# Iridium_9603_Beacon.net
KiCad netlist of a schematic drawn in EAGLE
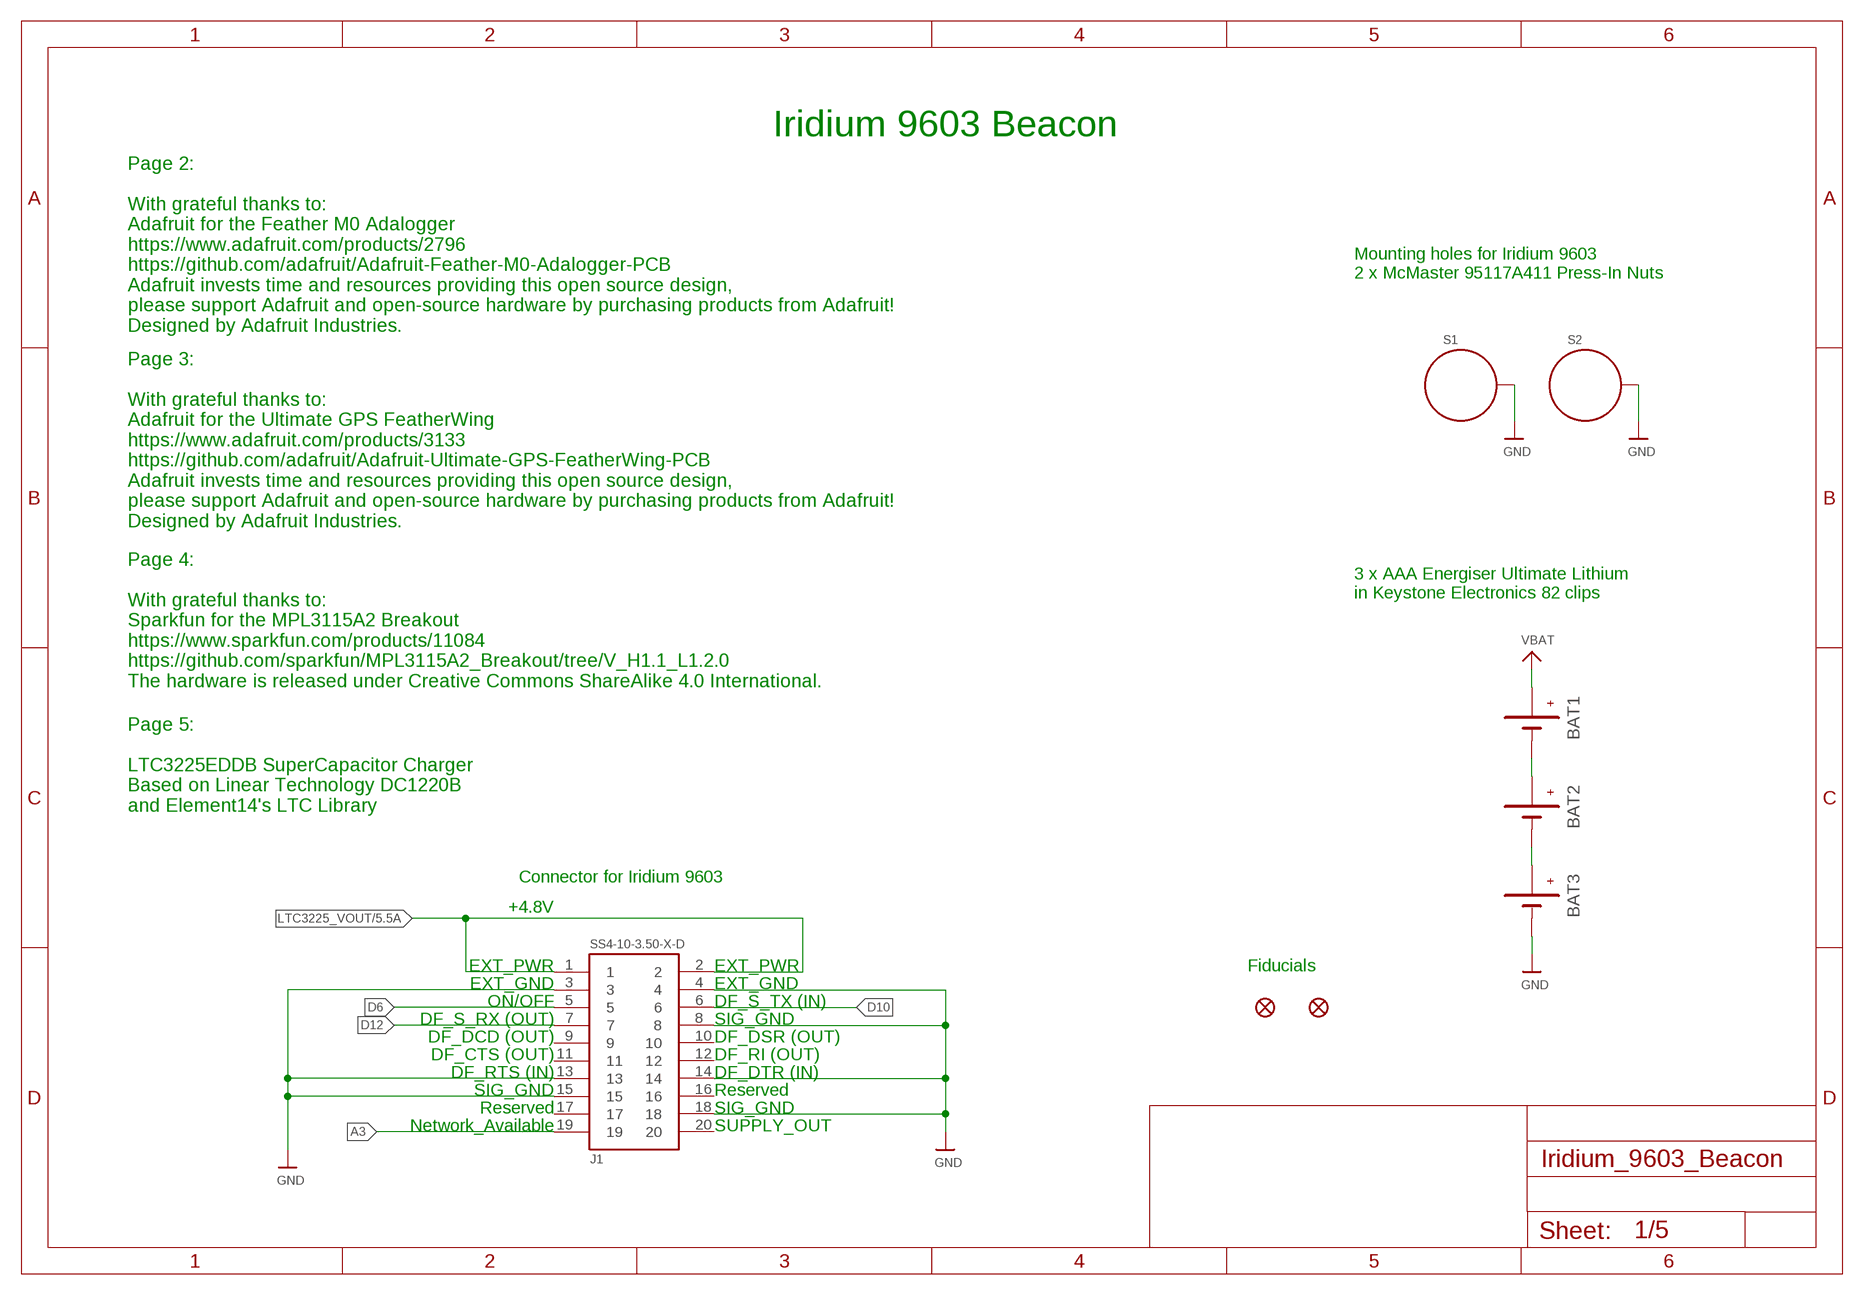
[diagram p0: schematic, sheet 1]
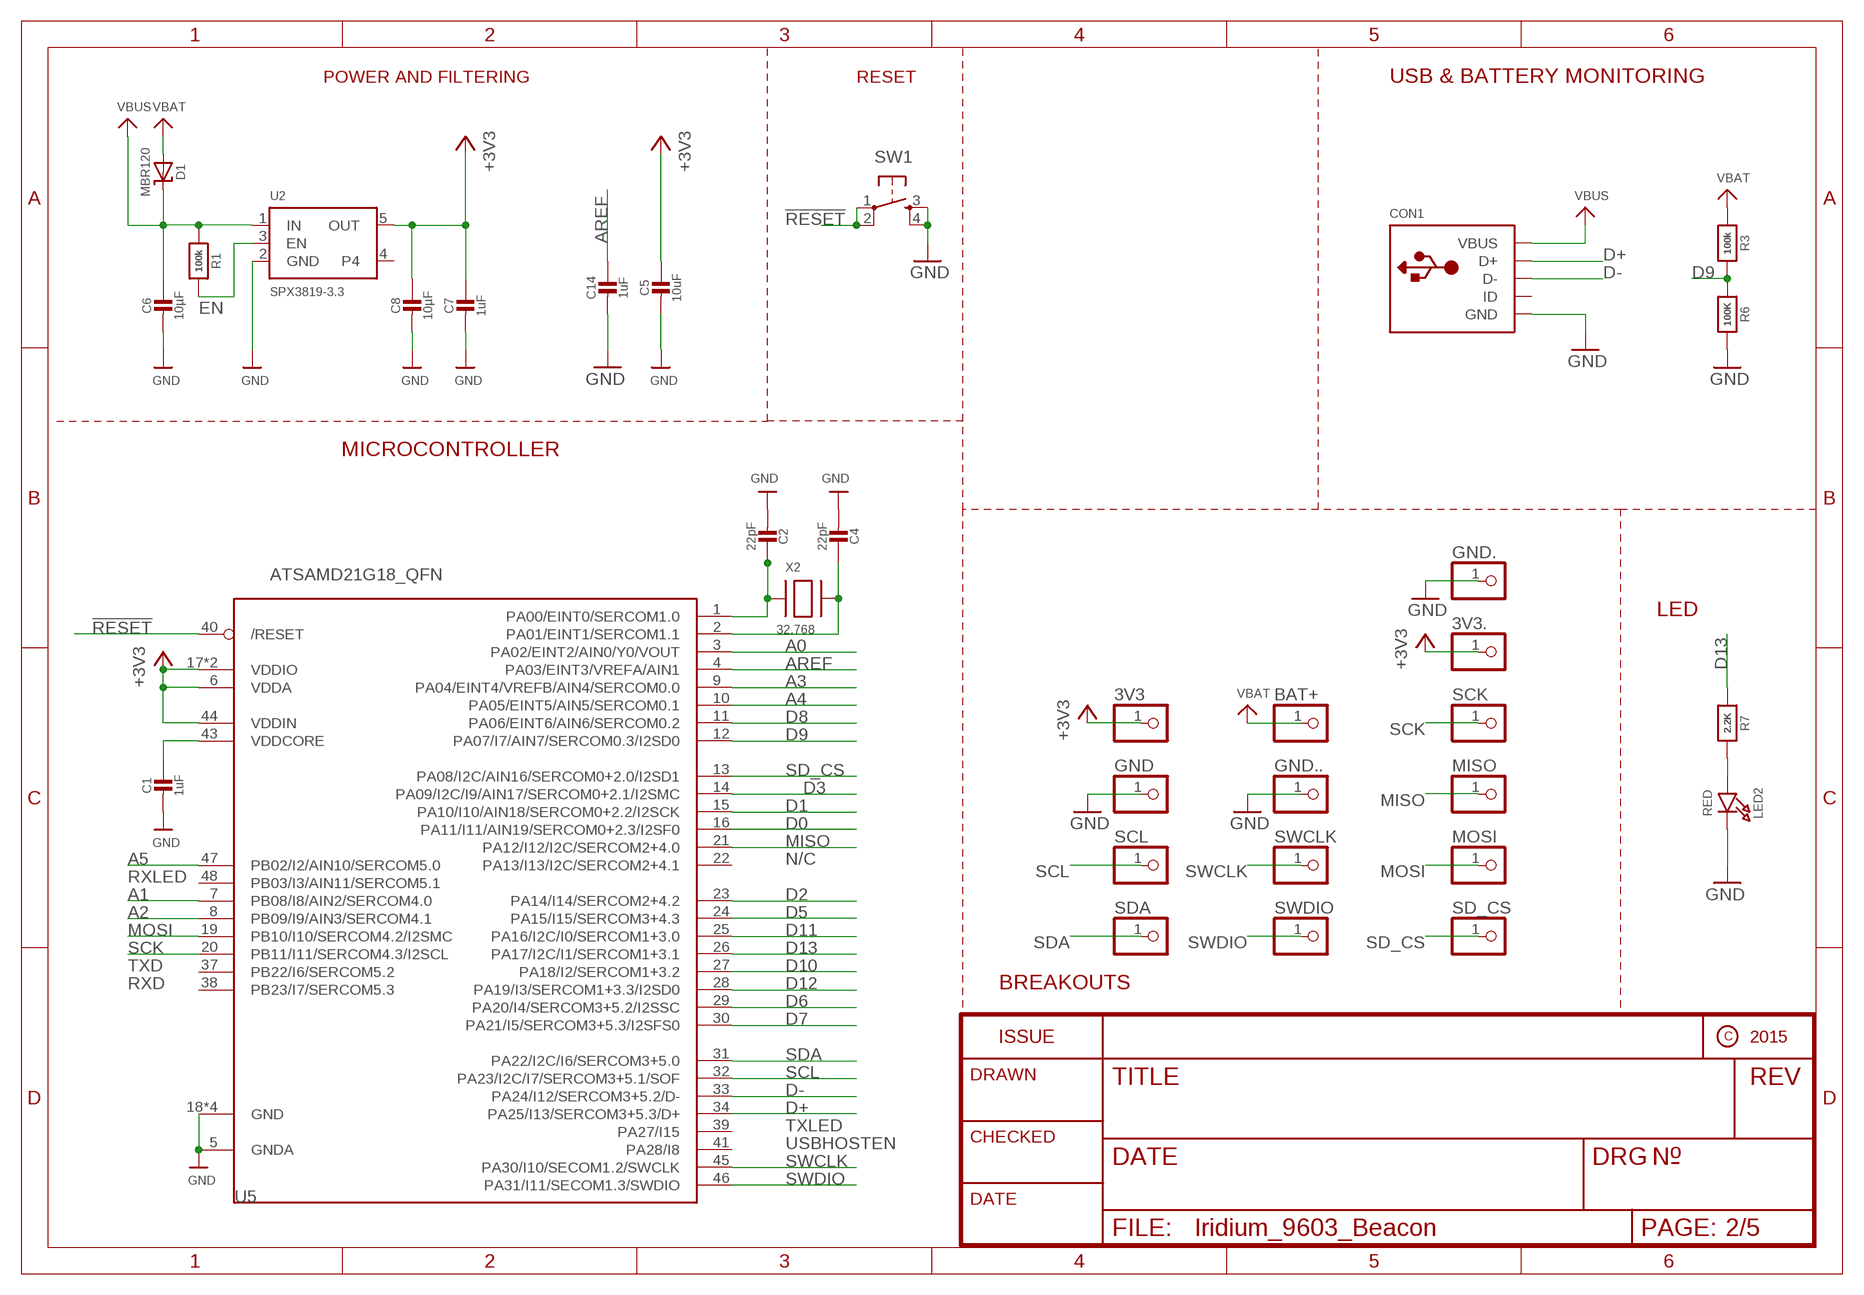
[diagram p1: schematic, sheet 2]
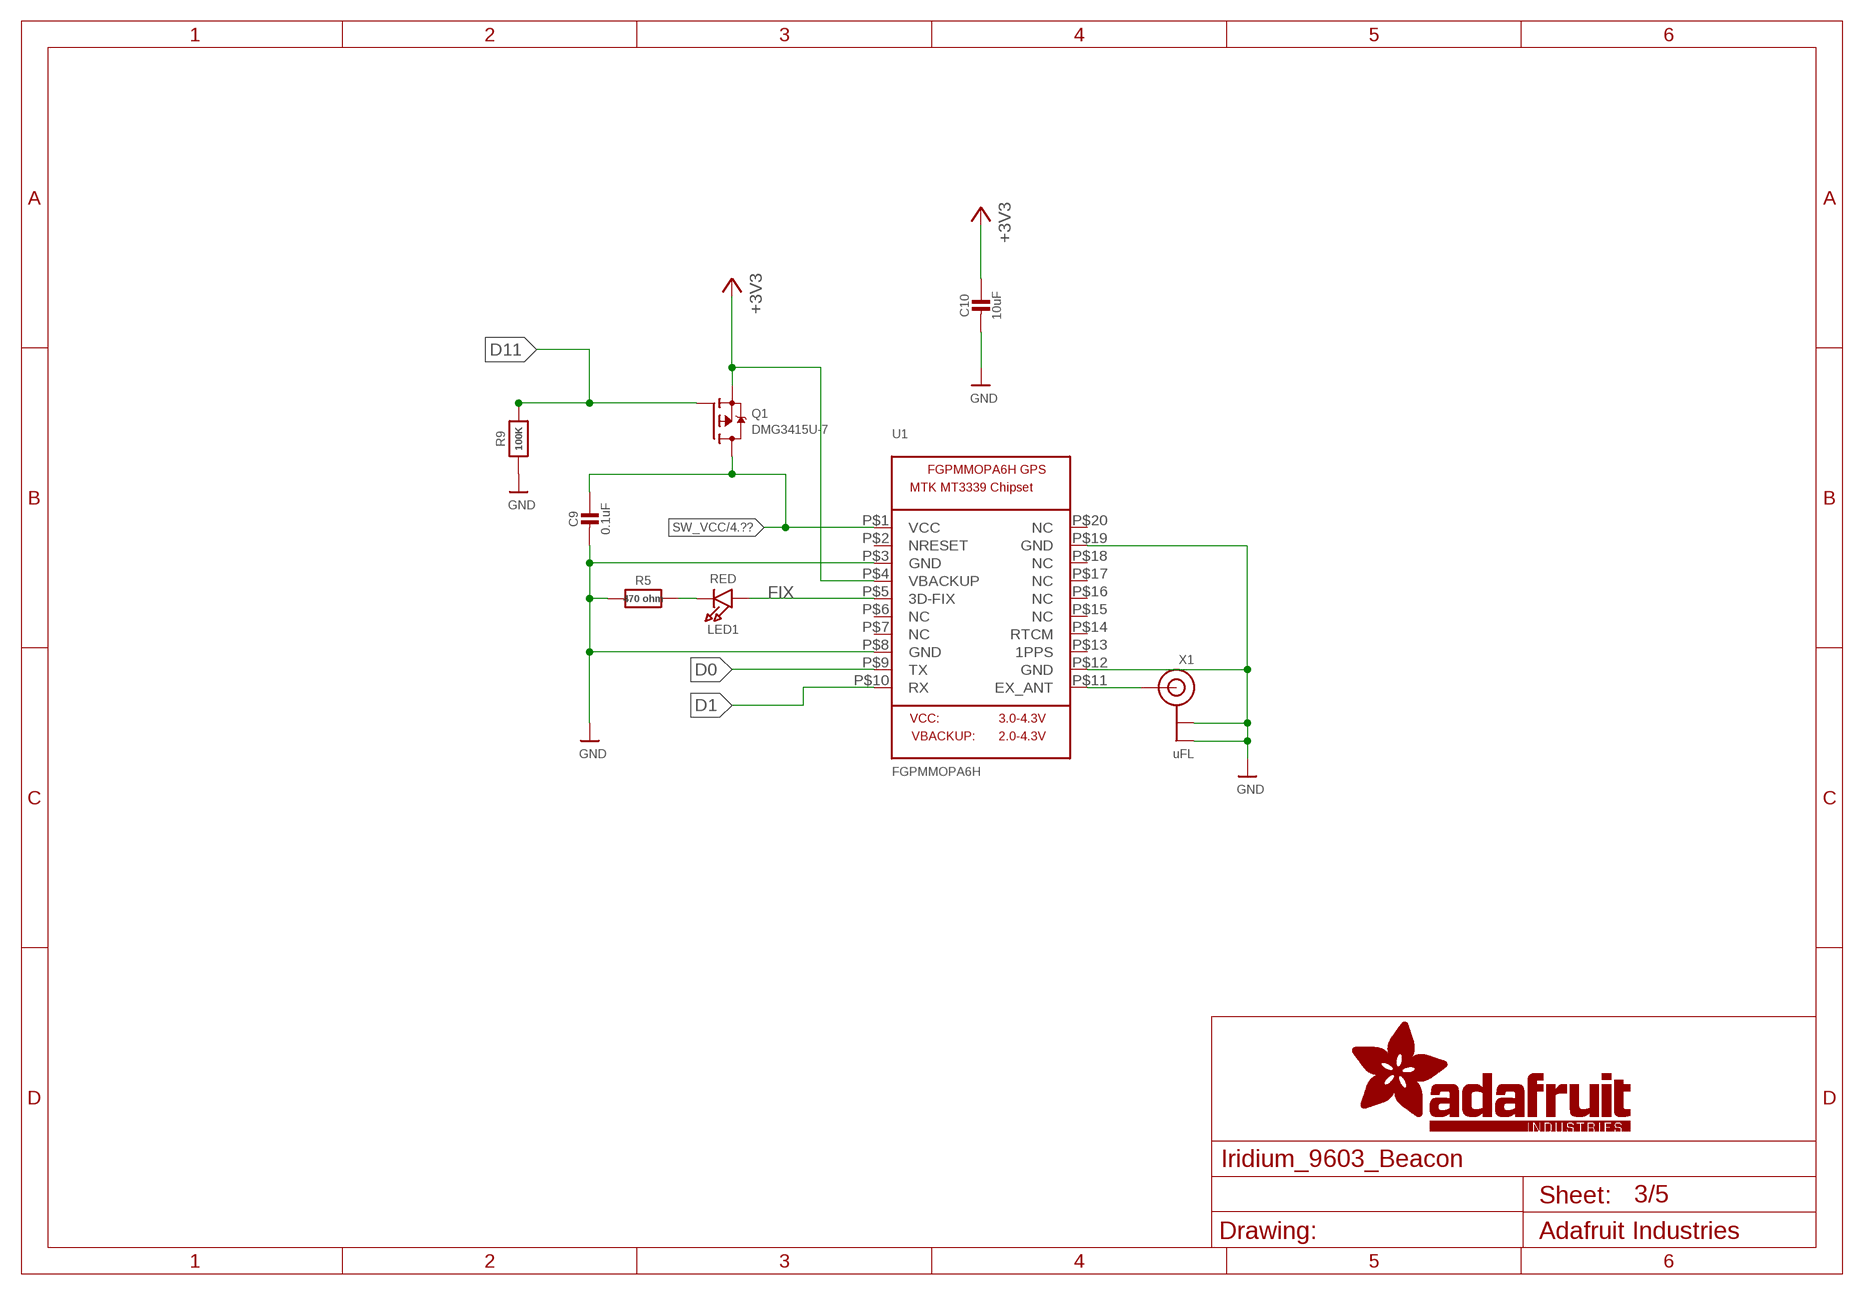
[diagram p2: schematic, sheet 3]
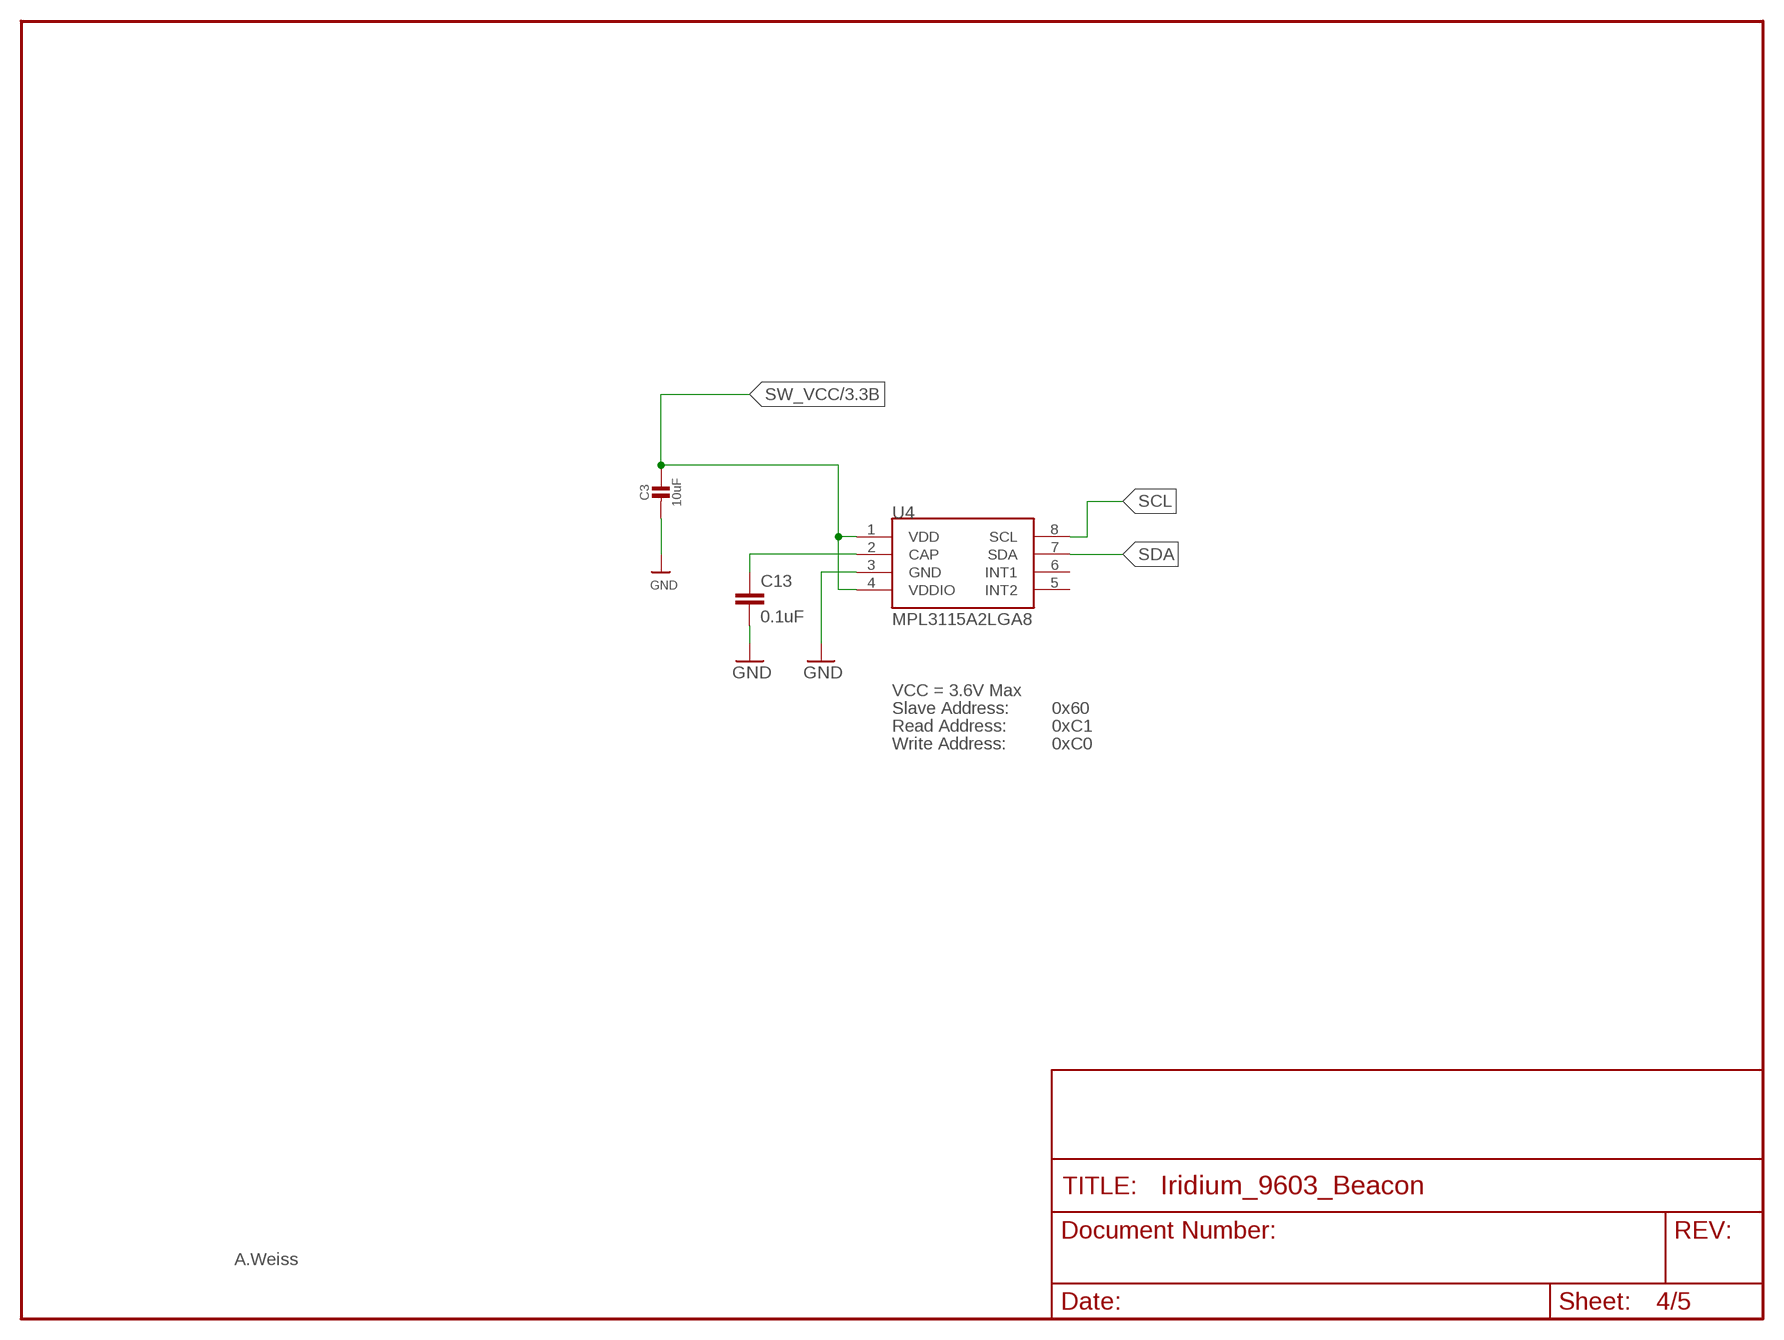
[diagram p3: schematic, sheet 4]
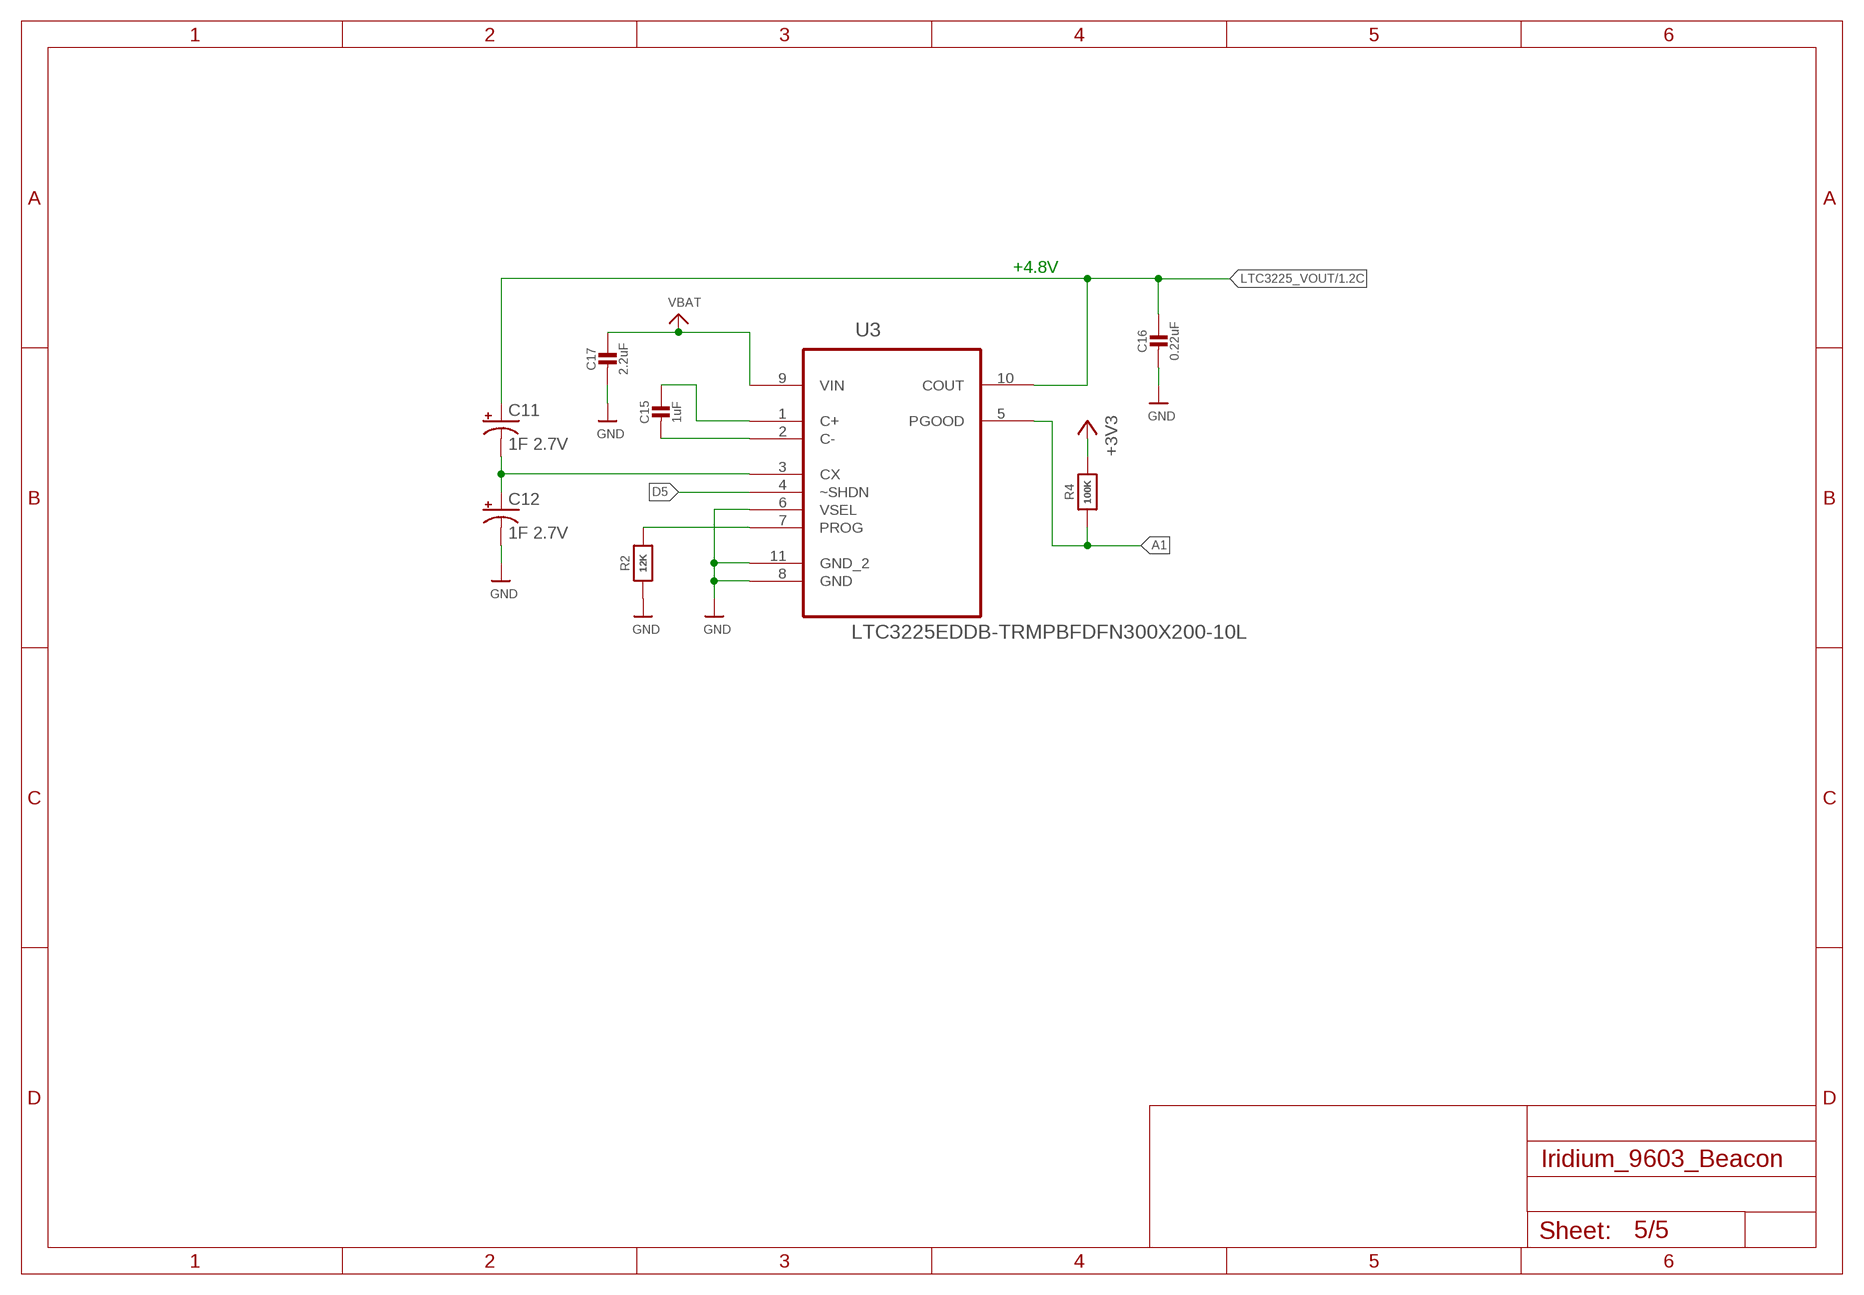
[diagram p4: schematic, sheet 5]

(export (version "E")
  (design (tool "Eeschema 10.0.6"))
  (components
    (comp (ref "C9")
      (value "0.1uF")
      (footprint "eagle-import:0805-NO")
      (libsource (lib "eagle-import") (part "CAP_CERAMIC0805-NOOUTLINE"))
    )
    (comp (ref "C10")
      (value "10uF")
      (footprint "eagle-import:0805-NO")
      (libsource (lib "eagle-import") (part "CAP_CERAMIC0805-NOOUTLINE"))
    )
    (comp (ref "LED1")
      (value "RED")
      (footprint "eagle-import:CHIPLED_0805_NOOUTLINE")
      (libsource (lib "eagle-import") (part "LED0805_NOOUTLINE"))
    )
    (comp (ref "Q1")
      (value "DMG3415U-7")
      (footprint "eagle-import:SOT23-WIDE")
      (libsource (lib "eagle-import") (part "MOSFET-PWIDE"))
    )
    (comp (ref "R5")
      (value "470 ohm")
      (footprint "eagle-import:0805-NO")
      (libsource (lib "eagle-import") (part "RESISTOR0805_NOOUTLINE"))
    )
    (comp (ref "R9")
      (value "100K")
      (footprint "eagle-import:0805-NO")
      (libsource (lib "eagle-import") (part "RESISTOR0805_NOOUTLINE"))
    )
    (comp (ref "U1")
      (value "FGPMMOPA6H")
      (footprint "eagle-import:FGPMMOPA6H")
      (libsource (lib "eagle-import") (part "GPS_FGPMMOPA6H"))
    )
    (comp (ref "X1")
      (value "uFL")
      (footprint "eagle-import:U.FL")
      (libsource (lib "eagle-import") (part "ANTENNA_U.FL"))
    )
    (comp (ref "C3")
      (value "10uF")
      (footprint "eagle-import:0805-NO")
      (libsource (lib "eagle-import") (part "CAP_CERAMIC0805-NOOUTLINE"))
    )
    (comp (ref "C13")
      (value "0.1uF")
      (footprint "eagle-import:0402-CAP")
      (libsource (lib "eagle-import") (part "CAP0402-CAP"))
    )
    (comp (ref "U4")
      (value "MPL3115A2LGA8")
      (footprint "eagle-import:LGA8")
      (libsource (lib "eagle-import") (part "MPL3115A2LGA8"))
    )
    (comp (ref "BAT1")
      (value "BATTERYKEYSTONE82")
      (footprint "eagle-import:BATTERY-AAA-KEYSTONE82")
      (libsource (lib "eagle-import") (part "BATTERYKEYSTONE82"))
    )
    (comp (ref "BAT2")
      (value "BATTERYKEYSTONE82")
      (footprint "eagle-import:BATTERY-AAA-KEYSTONE82")
      (libsource (lib "eagle-import") (part "BATTERYKEYSTONE82"))
    )
    (comp (ref "BAT3")
      (value "BATTERYKEYSTONE82")
      (footprint "eagle-import:BATTERY-AAA-KEYSTONE82")
      (libsource (lib "eagle-import") (part "BATTERYKEYSTONE82"))
    )
    (comp (ref "FD1")
      (value "FIDUCIAL1X2")
      (footprint "eagle-import:FIDUCIAL-1X2")
      (libsource (lib "eagle-import") (part "FIDUCIAL1X2"))
    )
    (comp (ref "FD2")
      (value "FIDUCIAL1X2")
      (footprint "eagle-import:FIDUCIAL-1X2")
      (libsource (lib "eagle-import") (part "FIDUCIAL1X2"))
    )
    (comp (ref "J1")
      (value "SS4-10-3.50-X-D")
      (footprint "eagle-import:SS4-10-3.50-X-D")
      (libsource (lib "eagle-import") (part "SS4-10-3.50-X-D"))
    )
    (comp (ref "S1")
      (value "STANDOFF_ELECTRICALMCMASTER-95117A411")
      (footprint "eagle-import:STANDOFF-ELECTRICAL-MCMASTER-95117A411")
      (libsource (lib "eagle-import") (part "STANDOFF_ELECTRICALMCMASTER-95117A411"))
    )
    (comp (ref "S2")
      (value "STANDOFF_ELECTRICALMCMASTER-95117A411")
      (footprint "eagle-import:STANDOFF-ELECTRICAL-MCMASTER-95117A411")
      (libsource (lib "eagle-import") (part "STANDOFF_ELECTRICALMCMASTER-95117A411"))
    )
    (comp (ref "C11")
      (value "1F 2.7V")
      (footprint "eagle-import:CPOL-RADIAL-1F-2.7V")
      (libsource (lib "eagle-import") (part "1F-2.7V(PTH)CPOL-RADIAL-1H-2.7V"))
    )
    (comp (ref "C12")
      (value "1F 2.7V")
      (footprint "eagle-import:CPOL-RADIAL-1F-2.7V")
      (libsource (lib "eagle-import") (part "1F-2.7V(PTH)CPOL-RADIAL-1H-2.7V"))
    )
    (comp (ref "C15")
      (value "1uF")
      (footprint "eagle-import:0603-NO")
      (libsource (lib "eagle-import") (part "CAP_CERAMIC0603_NO"))
    )
    (comp (ref "C16")
      (value "0.22uF")
      (footprint "eagle-import:0603-NO")
      (libsource (lib "eagle-import") (part "CAP_CERAMIC0603_NO"))
    )
    (comp (ref "C17")
      (value "2.2uF")
      (footprint "eagle-import:0805-NO")
      (libsource (lib "eagle-import") (part "CAP_CERAMIC0805-NOOUTLINE"))
    )
    (comp (ref "R2")
      (value "12K")
      (footprint "eagle-import:0805-NO")
      (libsource (lib "eagle-import") (part "RESISTOR0805_NOOUTLINE"))
    )
    (comp (ref "R4")
      (value "100K")
      (footprint "eagle-import:0805-NO")
      (libsource (lib "eagle-import") (part "RESISTOR0805_NOOUTLINE"))
    )
    (comp (ref "U3")
      (value "LTC3225EDDB-TRMPBFDFN300X200-10L")
      (footprint "eagle-import:DFN300X200-10L")
      (libsource (lib "eagle-import") (part "LTC3225EDDB-TRMPBFDFN300X200-10L"))
    )
    (comp (ref "3V3")
      (value "PINHD-1X1")
      (footprint "eagle-import:1X01")
      (libsource (lib "eagle-import") (part "PINHD-1X1"))
    )
    (comp (ref "3V3.")
      (value "PINHD-1X1")
      (footprint "eagle-import:1X01")
      (libsource (lib "eagle-import") (part "PINHD-1X1"))
    )
    (comp (ref "BAT+")
      (value "PINHD-1X1")
      (footprint "eagle-import:1X01")
      (libsource (lib "eagle-import") (part "PINHD-1X1"))
    )
    (comp (ref "C1")
      (value "1uF")
      (footprint "eagle-import:0603-NO")
      (libsource (lib "eagle-import") (part "CAP_CERAMIC0603_NO"))
    )
    (comp (ref "C2")
      (value "22pF")
      (footprint "eagle-import:0603-NO")
      (libsource (lib "eagle-import") (part "CAP_CERAMIC0603_NO"))
    )
    (comp (ref "C4")
      (value "22pF")
      (footprint "eagle-import:0603-NO")
      (libsource (lib "eagle-import") (part "CAP_CERAMIC0603_NO"))
    )
    (comp (ref "C5")
      (value "10uF")
      (footprint "eagle-import:0805-NO")
      (libsource (lib "eagle-import") (part "CAP_CERAMIC0805-NOOUTLINE"))
    )
    (comp (ref "C6")
      (value "10µF")
      (footprint "eagle-import:0805-NO")
      (libsource (lib "eagle-import") (part "CAP_CERAMIC0805-NOOUTLINE"))
    )
    (comp (ref "C7")
      (value "1uF")
      (footprint "eagle-import:0603-NO")
      (libsource (lib "eagle-import") (part "CAP_CERAMIC0603_NO"))
    )
    (comp (ref "C8")
      (value "10µF")
      (footprint "eagle-import:0805-NO")
      (libsource (lib "eagle-import") (part "CAP_CERAMIC0805-NOOUTLINE"))
    )
    (comp (ref "C14")
      (value "1uF")
      (footprint "eagle-import:0603-NO")
      (libsource (lib "eagle-import") (part "CAP_CERAMIC0603_NO"))
    )
    (comp (ref "CON1")
      (value "USBFCI_10103594")
      (footprint "eagle-import:FCI_10103594")
      (libsource (lib "eagle-import") (part "USBFCI_10103594"))
    )
    (comp (ref "D1")
      (value "MBR120")
      (footprint "eagle-import:SOD-123")
      (libsource (lib "eagle-import") (part "DIODE-SCHOTTKYSOD-123"))
    )
    (comp (ref "GND")
      (value "PINHD-1X1")
      (footprint "eagle-import:1X01")
      (libsource (lib "eagle-import") (part "PINHD-1X1"))
    )
    (comp (ref "GND.")
      (value "PINHD-1X1")
      (footprint "eagle-import:1X01")
      (libsource (lib "eagle-import") (part "PINHD-1X1"))
    )
    (comp (ref "GND..")
      (value "PINHD-1X1")
      (footprint "eagle-import:1X01")
      (libsource (lib "eagle-import") (part "PINHD-1X1"))
    )
    (comp (ref "LED2")
      (value "RED")
      (footprint "eagle-import:CHIPLED_0805_NOOUTLINE")
      (libsource (lib "eagle-import") (part "LED0805_NOOUTLINE"))
    )
    (comp (ref "MISO")
      (value "PINHD-1X1")
      (footprint "eagle-import:1X01")
      (libsource (lib "eagle-import") (part "PINHD-1X1"))
    )
    (comp (ref "MOSI")
      (value "PINHD-1X1")
      (footprint "eagle-import:1X01")
      (libsource (lib "eagle-import") (part "PINHD-1X1"))
    )
    (comp (ref "R1")
      (value "100k")
      (footprint "eagle-import:0603-NO")
      (libsource (lib "eagle-import") (part "RESISTOR_0603_NOOUT"))
    )
    (comp (ref "R3")
      (value "100k")
      (footprint "eagle-import:0603-NO")
      (libsource (lib "eagle-import") (part "RESISTOR_0603_NOOUT"))
    )
    (comp (ref "R6")
      (value "100K")
      (footprint "eagle-import:0603-NO")
      (libsource (lib "eagle-import") (part "RESISTOR_0603_NOOUT"))
    )
    (comp (ref "R7")
      (value "2.2K")
      (footprint "eagle-import:0603-NO")
      (libsource (lib "eagle-import") (part "RESISTOR_0603_NOOUT"))
    )
    (comp (ref "SCK")
      (value "PINHD-1X1")
      (footprint "eagle-import:1X01")
      (libsource (lib "eagle-import") (part "PINHD-1X1"))
    )
    (comp (ref "SCL")
      (value "PINHD-1X1")
      (footprint "eagle-import:1X01")
      (libsource (lib "eagle-import") (part "PINHD-1X1"))
    )
    (comp (ref "SDA")
      (value "PINHD-1X1")
      (footprint "eagle-import:1X01")
      (libsource (lib "eagle-import") (part "PINHD-1X1"))
    )
    (comp (ref "SD_CS")
      (value "PINHD-1X1")
      (footprint "eagle-import:1X01")
      (libsource (lib "eagle-import") (part "PINHD-1X1"))
    )
    (comp (ref "SW1")
      (value "SWITCH_SPST_4_PINRECT")
      (footprint "eagle-import:TACTILE_SWITCH_SMD_4.6X2.8MM")
      (libsource (lib "eagle-import") (part "SWITCH_SPST_4_PINRECT"))
    )
    (comp (ref "SWCLK")
      (value "PINHD-1X1")
      (footprint "eagle-import:1X01")
      (libsource (lib "eagle-import") (part "PINHD-1X1"))
    )
    (comp (ref "SWDIO")
      (value "PINHD-1X1")
      (footprint "eagle-import:1X01")
      (libsource (lib "eagle-import") (part "PINHD-1X1"))
    )
    (comp (ref "U2")
      (value "SPX3819-3.3")
      (footprint "eagle-import:SOT23-5")
      (libsource (lib "eagle-import") (part "VREG_SOT23-5"))
    )
    (comp (ref "U5")
      (value "ATSAMD21G18_QFN")
      (footprint "eagle-import:TQFN48_7MM")
      (libsource (lib "eagle-import") (part "ATSAMD21J_QFN"))
    )
    (comp (ref "X2")
      (value "32.768")
      (footprint "eagle-import:XTAL3215")
      (libsource (lib "eagle-import") (part "XTAL-3.2X1.5"))
    )
  )
  (nets
    (net (code "1") (name "+3V3") (class "Default")
      (node (ref "3V3") (pin "1") (pinfunction "1_1") (pintype "passive"))
      (node (ref "3V3.") (pin "1") (pinfunction "1_1") (pintype "passive"))
      (node (ref "C10") (pin "1") (pinfunction "1_1") (pintype "passive"))
      (node (ref "C5") (pin "1") (pinfunction "1_1") (pintype "passive"))
      (node (ref "C7") (pin "1") (pinfunction "1_1") (pintype "passive"))
      (node (ref "C8") (pin "1") (pinfunction "1_1") (pintype "passive"))
      (node (ref "Q1") (pin "2") (pinfunction "S_2") (pintype "passive"))
      (node (ref "R4") (pin "2") (pinfunction "2_2") (pintype "passive"))
      (node (ref "U1") (pin "P$4") (pinfunction "VBACKUP_P$4") (pintype "bidirectional"))
      (node (ref "U2") (pin "5") (pinfunction "OUT_5") (pintype "power_in"))
      (node (ref "U5") (pin "17") (pinfunction "VDDIO_17") (pintype "power_in"))
      (node (ref "U5") (pin "36") (pinfunction "VDDIO_36") (pintype "power_in"))
      (node (ref "U5") (pin "44") (pinfunction "VDDIN_44") (pintype "power_in"))
      (node (ref "U5") (pin "6") (pinfunction "VDDA_6") (pintype "power_in"))
    )
    (net (code "2") (name "A0") (class "Default")
      (node (ref "U5") (pin "3") (pinfunction "PA02/EINT2/AIN0/Y0/VOUT_3") (pintype "bidirectional"))
    )
    (net (code "3") (name "A1") (class "Default")
      (node (ref "R4") (pin "1") (pinfunction "1_1") (pintype "passive"))
      (node (ref "U3") (pin "5") (pinfunction "PGOOD_5") (pintype "output"))
      (node (ref "U5") (pin "7") (pinfunction "PB08/I8/AIN2/SERCOM4.0_7") (pintype "bidirectional"))
    )
    (net (code "4") (name "A2") (class "Default")
      (node (ref "U5") (pin "8") (pinfunction "PB09/I9/AIN3/SERCOM4.1_8") (pintype "bidirectional"))
    )
    (net (code "5") (name "A3") (class "Default")
      (node (ref "J1") (pin "19") (pinfunction "19_19") (pintype "bidirectional"))
      (node (ref "U5") (pin "9") (pinfunction "PA04/EINT4/VREFB/AIN4/SERCOM0.0_9") (pintype "bidirectional"))
    )
    (net (code "6") (name "A4") (class "Default")
      (node (ref "U5") (pin "10") (pinfunction "PA05/EINT5/AIN5/SERCOM0.1_10") (pintype "bidirectional"))
    )
    (net (code "7") (name "A5") (class "Default")
      (node (ref "U5") (pin "47") (pinfunction "PB02/I2/AIN10/SERCOM5.0_47") (pintype "bidirectional"))
    )
    (net (code "8") (name "AREF") (class "Default")
      (node (ref "C14") (pin "1") (pinfunction "1_1") (pintype "passive"))
      (node (ref "U5") (pin "4") (pinfunction "PA03/EINT3/VREFA/AIN1_4") (pintype "bidirectional"))
    )
    (net (code "9") (name "D+") (class "Default")
      (node (ref "CON1") (pin "D+") (pinfunction "D+_D+") (pintype "bidirectional"))
      (node (ref "U5") (pin "34") (pinfunction "PA25/I13/SERCOM3+5.3/D+_34") (pintype "bidirectional"))
    )
    (net (code "10") (name "D-") (class "Default")
      (node (ref "CON1") (pin "D-") (pinfunction "D-_D-") (pintype "bidirectional"))
      (node (ref "U5") (pin "33") (pinfunction "PA24/I12/SERCOM3+5.2/D-_33") (pintype "bidirectional"))
    )
    (net (code "11") (name "D0") (class "Default")
      (node (ref "U1") (pin "P$9") (pinfunction "TX_P$9") (pintype "bidirectional"))
      (node (ref "U5") (pin "16") (pinfunction "PA11/I11/AIN19/SERCOM0+2.3/I2SF0_16") (pintype "bidirectional"))
    )
    (net (code "12") (name "D1") (class "Default")
      (node (ref "U1") (pin "P$10") (pinfunction "RX_P$10") (pintype "bidirectional"))
      (node (ref "U5") (pin "15") (pinfunction "PA10/I10/AIN18/SERCOM0+2.2/I2SCK_15") (pintype "bidirectional"))
    )
    (net (code "13") (name "D2") (class "Default")
      (node (ref "U5") (pin "23") (pinfunction "PA14/I14/SERCOM2+4.2_23") (pintype "bidirectional"))
    )
    (net (code "14") (name "D3") (class "Default")
      (node (ref "U5") (pin "14") (pinfunction "PA09/I2C/I9/AIN17/SERCOM0+2.1/I2SMC_14") (pintype "bidirectional"))
    )
    (net (code "15") (name "D5") (class "Default")
      (node (ref "U3") (pin "4") (pinfunction "~{SHDN}_4") (pintype "input"))
      (node (ref "U5") (pin "24") (pinfunction "PA15/I15/SERCOM3+4.3_24") (pintype "bidirectional"))
    )
    (net (code "16") (name "D6") (class "Default")
      (node (ref "J1") (pin "5") (pinfunction "5_5") (pintype "bidirectional"))
      (node (ref "U5") (pin "29") (pinfunction "PA20/I4/SERCOM3+5.2/I2SSC_29") (pintype "bidirectional"))
    )
    (net (code "17") (name "D7") (class "Default")
      (node (ref "U5") (pin "30") (pinfunction "PA21/I5/SERCOM3+5.3/I2SFS0_30") (pintype "bidirectional"))
    )
    (net (code "18") (name "D8") (class "Default")
      (node (ref "U5") (pin "11") (pinfunction "PA06/EINT6/AIN6/SERCOM0.2_11") (pintype "bidirectional"))
    )
    (net (code "19") (name "D9") (class "Default")
      (node (ref "R3") (pin "2") (pinfunction "2_2") (pintype "passive"))
      (node (ref "R6") (pin "1") (pinfunction "1_1") (pintype "passive"))
      (node (ref "U5") (pin "12") (pinfunction "PA07/I7/AIN7/SERCOM0.3/I2SD0_12") (pintype "bidirectional"))
    )
    (net (code "20") (name "D10") (class "Default")
      (node (ref "J1") (pin "6") (pinfunction "6_6") (pintype "bidirectional"))
      (node (ref "U5") (pin "27") (pinfunction "PA18/I2/SERCOM1+3.2_27") (pintype "bidirectional"))
    )
    (net (code "21") (name "D11") (class "Default")
      (node (ref "Q1") (pin "1") (pinfunction "G_1") (pintype "passive"))
      (node (ref "R9") (pin "2") (pinfunction "2_2") (pintype "passive"))
      (node (ref "U5") (pin "25") (pinfunction "PA16/I2C/I0/SERCOM1+3.0_25") (pintype "bidirectional"))
    )
    (net (code "22") (name "D12") (class "Default")
      (node (ref "J1") (pin "7") (pinfunction "7_7") (pintype "bidirectional"))
      (node (ref "U5") (pin "28") (pinfunction "PA19/I3/SERCOM1+3.3/I2SD0_28") (pintype "bidirectional"))
    )
    (net (code "23") (name "D13") (class "Default")
      (node (ref "R7") (pin "1") (pinfunction "1_1") (pintype "passive"))
      (node (ref "U5") (pin "26") (pinfunction "PA17/I2C/I1/SERCOM1+3.1_26") (pintype "bidirectional"))
    )
    (net (code "24") (name "EN") (class "Default")
      (node (ref "R1") (pin "2") (pinfunction "2_2") (pintype "passive"))
      (node (ref "U2") (pin "3") (pinfunction "EN_3") (pintype "input"))
    )
    (net (code "25") (name "FIX") (class "Default")
      (node (ref "LED1") (pin "A") (pinfunction "A_A") (pintype "passive"))
      (node (ref "U1") (pin "P$5") (pinfunction "3D-FIX_P$5") (pintype "bidirectional"))
    )
    (net (code "26") (name "GND") (class "Default")
      (node (ref "BAT3") (pin "GND@1") (pinfunction "-_GND@1") (pintype "power_in"))
      (node (ref "BAT3") (pin "GND@2") (pinfunction "-_GND@2") (pintype "power_in"))
      (node (ref "C1") (pin "2") (pinfunction "2_2") (pintype "passive"))
      (node (ref "C10") (pin "2") (pinfunction "2_2") (pintype "passive"))
      (node (ref "C12") (pin "-") (pinfunction "-_-") (pintype "passive"))
      (node (ref "C13") (pin "2") (pinfunction "2_2") (pintype "passive"))
      (node (ref "C14") (pin "2") (pinfunction "2_2") (pintype "passive"))
      (node (ref "C16") (pin "2") (pinfunction "2_2") (pintype "passive"))
      (node (ref "C17") (pin "2") (pinfunction "2_2") (pintype "passive"))
      (node (ref "C2") (pin "2") (pinfunction "2_2") (pintype "passive"))
      (node (ref "C3") (pin "2") (pinfunction "2_2") (pintype "passive"))
      (node (ref "C4") (pin "2") (pinfunction "2_2") (pintype "passive"))
      (node (ref "C5") (pin "2") (pinfunction "2_2") (pintype "passive"))
      (node (ref "C6") (pin "2") (pinfunction "2_2") (pintype "passive"))
      (node (ref "C7") (pin "2") (pinfunction "2_2") (pintype "passive"))
      (node (ref "C8") (pin "2") (pinfunction "2_2") (pintype "passive"))
      (node (ref "C9") (pin "2") (pinfunction "2_2") (pintype "passive"))
      (node (ref "CON1") (pin "BASE@1") (pinfunction "GND_BASE@1") (pintype "power_in"))
      (node (ref "CON1") (pin "BASE@2") (pinfunction "GND_BASE@2") (pintype "power_in"))
      (node (ref "CON1") (pin "GND") (pinfunction "GND_GND") (pintype "power_in"))
      (node (ref "CON1") (pin "SPRT@1") (pinfunction "GND_SPRT@1") (pintype "power_in"))
      (node (ref "CON1") (pin "SPRT@2") (pinfunction "GND_SPRT@2") (pintype "power_in"))
      (node (ref "CON1") (pin "SPRT@3") (pinfunction "GND_SPRT@3") (pintype "power_in"))
      (node (ref "CON1") (pin "SPRT@4") (pinfunction "GND_SPRT@4") (pintype "power_in"))
      (node (ref "GND") (pin "1") (pinfunction "1_1") (pintype "passive"))
      (node (ref "GND.") (pin "1") (pinfunction "1_1") (pintype "passive"))
      (node (ref "GND..") (pin "1") (pinfunction "1_1") (pintype "passive"))
      (node (ref "J1") (pin "13") (pinfunction "13_13") (pintype "bidirectional"))
      (node (ref "J1") (pin "14") (pinfunction "14_14") (pintype "bidirectional"))
      (node (ref "J1") (pin "15") (pinfunction "15_15") (pintype "bidirectional"))
      (node (ref "J1") (pin "18") (pinfunction "18_18") (pintype "bidirectional"))
      (node (ref "J1") (pin "3") (pinfunction "3_3") (pintype "bidirectional"))
      (node (ref "J1") (pin "4") (pinfunction "4_4") (pintype "bidirectional"))
      (node (ref "J1") (pin "8") (pinfunction "8_8") (pintype "bidirectional"))
      (node (ref "LED2") (pin "C") (pinfunction "C_C") (pintype "passive"))
      (node (ref "R2") (pin "1") (pinfunction "1_1") (pintype "passive"))
      (node (ref "R5") (pin "1") (pinfunction "1_1") (pintype "passive"))
      (node (ref "R6") (pin "2") (pinfunction "2_2") (pintype "passive"))
      (node (ref "R9") (pin "1") (pinfunction "1_1") (pintype "passive"))
      (node (ref "S1") (pin "P1") (pinfunction "P$1_P1") (pintype "bidirectional"))
      (node (ref "S2") (pin "P1") (pinfunction "P$1_P1") (pintype "bidirectional"))
      (node (ref "SW1") (pin "3") (pinfunction "3_3") (pintype "passive"))
      (node (ref "SW1") (pin "4") (pinfunction "4_4") (pintype "passive"))
      (node (ref "U1") (pin "P$12") (pinfunction "GND_P$12") (pintype "bidirectional"))
      (node (ref "U1") (pin "P$19") (pinfunction "GND_P$19") (pintype "bidirectional"))
      (node (ref "U1") (pin "P$3") (pinfunction "GND_P$3") (pintype "bidirectional"))
      (node (ref "U1") (pin "P$8") (pinfunction "GND_P$8") (pintype "bidirectional"))
      (node (ref "U2") (pin "2") (pinfunction "GND_2") (pintype "power_in"))
      (node (ref "U3") (pin "11") (pinfunction "GND_2_11") (pintype "passive"))
      (node (ref "U3") (pin "6") (pinfunction "VSEL_6") (pintype "input"))
      (node (ref "U3") (pin "8") (pinfunction "GND_8") (pintype "passive"))
      (node (ref "U4") (pin "3") (pinfunction "GND_3") (pintype "bidirectional"))
      (node (ref "U5") (pin "18") (pinfunction "GND_18") (pintype "power_in"))
      (node (ref "U5") (pin "35") (pinfunction "GND_35") (pintype "power_in"))
      (node (ref "U5") (pin "42") (pinfunction "GND_42") (pintype "power_in"))
      (node (ref "U5") (pin "5") (pinfunction "GNDA_5") (pintype "power_in"))
      (node (ref "U5") (pin "THERMAL") (pinfunction "GND_THERMAL") (pintype "power_in"))
      (node (ref "X1") (pin "1") (pinfunction "GND_1") (pintype "passive"))
      (node (ref "X1") (pin "2") (pinfunction "GND_2") (pintype "passive"))
    )
    (net (code "27") (name "LTC3225_VOUT") (class "Default")
      (node (ref "C11") (pin "+") (pinfunction "+_+") (pintype "passive"))
      (node (ref "C16") (pin "1") (pinfunction "1_1") (pintype "passive"))
      (node (ref "J1") (pin "1") (pinfunction "1_1") (pintype "bidirectional"))
      (node (ref "J1") (pin "2") (pinfunction "2_2") (pintype "bidirectional"))
      (node (ref "U3") (pin "10") (pinfunction "COUT_10") (pintype "output"))
    )
    (net (code "28") (name "MISO") (class "Default")
      (node (ref "MISO") (pin "1") (pinfunction "1_1") (pintype "passive"))
      (node (ref "U5") (pin "21") (pinfunction "PA12/I12/I2C/SERCOM2+4.0_21") (pintype "bidirectional"))
    )
    (net (code "29") (name "MOSI") (class "Default")
      (node (ref "MOSI") (pin "1") (pinfunction "1_1") (pintype "passive"))
      (node (ref "U5") (pin "19") (pinfunction "PB10/I10/SERCOM4.2/I2SMC_19") (pintype "bidirectional"))
    )
    (net (code "30") (name "Net-(BAT1---PadGND@1)") (class "Default")
      (node (ref "BAT1") (pin "GND@1") (pinfunction "-_GND@1") (pintype "power_in"))
      (node (ref "BAT1") (pin "GND@2") (pinfunction "-_GND@2") (pintype "power_in"))
      (node (ref "BAT2") (pin "PWR@1") (pinfunction "+_PWR@1") (pintype "power_in"))
      (node (ref "BAT2") (pin "PWR@2") (pinfunction "+_PWR@2") (pintype "power_in"))
    )
    (net (code "31") (name "Net-(BAT2---PadGND@1)") (class "Default")
      (node (ref "BAT2") (pin "GND@1") (pinfunction "-_GND@1") (pintype "power_in"))
      (node (ref "BAT2") (pin "GND@2") (pinfunction "-_GND@2") (pintype "power_in"))
      (node (ref "BAT3") (pin "PWR@1") (pinfunction "+_PWR@1") (pintype "power_in"))
      (node (ref "BAT3") (pin "PWR@2") (pinfunction "+_PWR@2") (pintype "power_in"))
    )
    (net (code "32") (name "Net-(LED1-PadC)") (class "Default")
      (node (ref "LED1") (pin "C") (pinfunction "C_C") (pintype "passive"))
      (node (ref "R5") (pin "2") (pinfunction "2_2") (pintype "passive"))
    )
    (net (code "33") (name "Net-(LED2-PadA)") (class "Default")
      (node (ref "LED2") (pin "A") (pinfunction "A_A") (pintype "passive"))
      (node (ref "R7") (pin "2") (pinfunction "2_2") (pintype "passive"))
    )
    (net (code "34") (name "Net-(U1-EX_ANT)") (class "Default")
      (node (ref "U1") (pin "P$11") (pinfunction "EX_ANT_P$11") (pintype "bidirectional"))
      (node (ref "X1") (pin "3") (pinfunction "SIGNAL_3") (pintype "passive"))
    )
    (net (code "35") (name "Net-(U3-C+)") (class "Default")
      (node (ref "C15") (pin "1") (pinfunction "1_1") (pintype "passive"))
      (node (ref "U3") (pin "1") (pinfunction "C+_1") (pintype "passive"))
    )
    (net (code "36") (name "Net-(U3-C-)") (class "Default")
      (node (ref "C15") (pin "2") (pinfunction "2_2") (pintype "passive"))
      (node (ref "U3") (pin "2") (pinfunction "C-_2") (pintype "passive"))
    )
    (net (code "37") (name "Net-(U3-CX)") (class "Default")
      (node (ref "C11") (pin "-") (pinfunction "-_-") (pintype "passive"))
      (node (ref "C12") (pin "+") (pinfunction "+_+") (pintype "passive"))
      (node (ref "U3") (pin "3") (pinfunction "CX_3") (pintype "passive"))
    )
    (net (code "38") (name "Net-(U3-PROG)") (class "Default")
      (node (ref "R2") (pin "2") (pinfunction "2_2") (pintype "passive"))
      (node (ref "U3") (pin "7") (pinfunction "PROG_7") (pintype "input"))
    )
    (net (code "39") (name "Net-(U4-CAP)") (class "Default")
      (node (ref "C13") (pin "1") (pinfunction "1_1") (pintype "passive"))
      (node (ref "U4") (pin "2") (pinfunction "CAP_2") (pintype "bidirectional"))
    )
    (net (code "40") (name "Net-(U5-PA00{slash}EINT0{slash}SERCOM1.0)") (class "Default")
      (node (ref "C2") (pin "1") (pinfunction "1_1") (pintype "passive"))
      (node (ref "U5") (pin "1") (pinfunction "PA00/EINT0/SERCOM1.0_1") (pintype "bidirectional"))
      (node (ref "X2") (pin "P$1") (pinfunction "P$1_P$1") (pintype "bidirectional"))
    )
    (net (code "41") (name "Net-(U5-PA01{slash}EINT1{slash}SERCOM1.1)") (class "Default")
      (node (ref "C4") (pin "1") (pinfunction "1_1") (pintype "passive"))
      (node (ref "U5") (pin "2") (pinfunction "PA01/EINT1/SERCOM1.1_2") (pintype "bidirectional"))
      (node (ref "X2") (pin "P$2") (pinfunction "P$2_P$2") (pintype "bidirectional"))
    )
    (net (code "42") (name "Net-(U5-VDDCORE)") (class "Default")
      (node (ref "C1") (pin "1") (pinfunction "1_1") (pintype "passive"))
      (node (ref "U5") (pin "43") (pinfunction "VDDCORE_43") (pintype "power_in"))
    )
    (net (code "43") (name "SCK") (class "Default")
      (node (ref "SCK") (pin "1") (pinfunction "1_1") (pintype "passive"))
      (node (ref "U5") (pin "20") (pinfunction "PB11/I11/SERCOM4.3/I2SCL_20") (pintype "bidirectional"))
    )
    (net (code "44") (name "SCL") (class "Default")
      (node (ref "SCL") (pin "1") (pinfunction "1_1") (pintype "passive"))
      (node (ref "U4") (pin "8") (pinfunction "SCL_8") (pintype "bidirectional"))
      (node (ref "U5") (pin "32") (pinfunction "PA23/I2C/I7/SERCOM3+5.1/SOF_32") (pintype "bidirectional"))
    )
    (net (code "45") (name "SDA") (class "Default")
      (node (ref "SDA") (pin "1") (pinfunction "1_1") (pintype "passive"))
      (node (ref "U4") (pin "7") (pinfunction "SDA_7") (pintype "bidirectional"))
      (node (ref "U5") (pin "31") (pinfunction "PA22/I2C/I6/SERCOM3+5.0_31") (pintype "bidirectional"))
    )
    (net (code "46") (name "SD_CS") (class "Default")
      (node (ref "SD_CS") (pin "1") (pinfunction "1_1") (pintype "passive"))
      (node (ref "U5") (pin "13") (pinfunction "PA08/I2C/AIN16/SERCOM0+2.0/I2SD1_13") (pintype "bidirectional"))
    )
    (net (code "47") (name "SWCLK") (class "Default")
      (node (ref "SWCLK") (pin "1") (pinfunction "1_1") (pintype "passive"))
      (node (ref "U5") (pin "45") (pinfunction "PA30/I10/SECOM1.2/SWCLK_45") (pintype "bidirectional"))
    )
    (net (code "48") (name "SWDIO") (class "Default")
      (node (ref "SWDIO") (pin "1") (pinfunction "1_1") (pintype "passive"))
      (node (ref "U5") (pin "46") (pinfunction "PA31/I11/SECOM1.3/SWDIO_46") (pintype "bidirectional"))
    )
    (net (code "49") (name "SW_VCC") (class "Default")
      (node (ref "C3") (pin "1") (pinfunction "1_1") (pintype "passive"))
      (node (ref "C9") (pin "1") (pinfunction "1_1") (pintype "passive"))
      (node (ref "Q1") (pin "3") (pinfunction "D_3") (pintype "passive"))
      (node (ref "U1") (pin "P$1") (pinfunction "VCC_P$1") (pintype "bidirectional"))
      (node (ref "U4") (pin "1") (pinfunction "VDD_1") (pintype "bidirectional"))
      (node (ref "U4") (pin "4") (pinfunction "VDDIO_4") (pintype "bidirectional"))
    )
    (net (code "50") (name "VBAT") (class "Default")
      (node (ref "BAT+") (pin "1") (pinfunction "1_1") (pintype "passive"))
      (node (ref "BAT1") (pin "PWR@1") (pinfunction "+_PWR@1") (pintype "power_in"))
      (node (ref "BAT1") (pin "PWR@2") (pinfunction "+_PWR@2") (pintype "power_in"))
      (node (ref "C17") (pin "1") (pinfunction "1_1") (pintype "passive"))
      (node (ref "D1") (pin "A") (pinfunction "A_A") (pintype "passive"))
      (node (ref "R3") (pin "1") (pinfunction "1_1") (pintype "passive"))
      (node (ref "U3") (pin "9") (pinfunction "VIN_9") (pintype "power_in"))
    )
    (net (code "51") (name "VBUS") (class "Default")
      (node (ref "C6") (pin "1") (pinfunction "1_1") (pintype "passive"))
      (node (ref "CON1") (pin "VBUS") (pinfunction "VBUS_VBUS") (pintype "power_in"))
      (node (ref "D1") (pin "C") (pinfunction "C_C") (pintype "passive"))
      (node (ref "R1") (pin "1") (pinfunction "1_1") (pintype "passive"))
      (node (ref "U2") (pin "1") (pinfunction "IN_1") (pintype "power_in"))
    )
    (net (code "52") (name "unconnected-(CON1-PadID)") (class "Default")
      (node (ref "CON1") (pin "ID") (pinfunction "ID_ID") (pintype "bidirectional"))
    )
    (net (code "53") (name "unconnected-(J1-Pad9)") (class "Default")
      (node (ref "J1") (pin "9") (pinfunction "9_9") (pintype "bidirectional"))
    )
    (net (code "54") (name "unconnected-(J1-Pad10)") (class "Default")
      (node (ref "J1") (pin "10") (pinfunction "10_10") (pintype "bidirectional"))
    )
    (net (code "55") (name "unconnected-(J1-Pad11)") (class "Default")
      (node (ref "J1") (pin "11") (pinfunction "11_11") (pintype "bidirectional"))
    )
    (net (code "56") (name "unconnected-(J1-Pad12)") (class "Default")
      (node (ref "J1") (pin "12") (pinfunction "12_12") (pintype "bidirectional"))
    )
    (net (code "57") (name "unconnected-(J1-Pad16)") (class "Default")
      (node (ref "J1") (pin "16") (pinfunction "16_16") (pintype "bidirectional"))
    )
    (net (code "58") (name "unconnected-(J1-Pad17)") (class "Default")
      (node (ref "J1") (pin "17") (pinfunction "17_17") (pintype "bidirectional"))
    )
    (net (code "59") (name "unconnected-(J1-Pad20)") (class "Default")
      (node (ref "J1") (pin "20") (pinfunction "20_20") (pintype "bidirectional"))
    )
    (net (code "60") (name "unconnected-(U1-1PPS-PadP$13)") (class "Default")
      (node (ref "U1") (pin "P$13") (pinfunction "1PPS_P$13") (pintype "bidirectional"))
    )
    (net (code "61") (name "unconnected-(U1-NC-PadP$6)") (class "Default")
      (node (ref "U1") (pin "P$6") (pinfunction "NC_P$6") (pintype "bidirectional"))
    )
    (net (code "62") (name "unconnected-(U1-NC-PadP$7)") (class "Default")
      (node (ref "U1") (pin "P$7") (pinfunction "NC_P$7") (pintype "bidirectional"))
    )
    (net (code "63") (name "unconnected-(U1-NC-PadP$15)") (class "Default")
      (node (ref "U1") (pin "P$15") (pinfunction "NC_P$15") (pintype "bidirectional"))
    )
    (net (code "64") (name "unconnected-(U1-NC-PadP$16)") (class "Default")
      (node (ref "U1") (pin "P$16") (pinfunction "NC_P$16") (pintype "bidirectional"))
    )
    (net (code "65") (name "unconnected-(U1-NC-PadP$17)") (class "Default")
      (node (ref "U1") (pin "P$17") (pinfunction "NC_P$17") (pintype "bidirectional"))
    )
    (net (code "66") (name "unconnected-(U1-NC-PadP$18)") (class "Default")
      (node (ref "U1") (pin "P$18") (pinfunction "NC_P$18") (pintype "bidirectional"))
    )
    (net (code "67") (name "unconnected-(U1-NC-PadP$20)") (class "Default")
      (node (ref "U1") (pin "P$20") (pinfunction "NC_P$20") (pintype "bidirectional"))
    )
    (net (code "68") (name "unconnected-(U1-NRESET-PadP$2)") (class "Default")
      (node (ref "U1") (pin "P$2") (pinfunction "NRESET_P$2") (pintype "bidirectional"))
    )
    (net (code "69") (name "unconnected-(U1-RTCM-PadP$14)") (class "Default")
      (node (ref "U1") (pin "P$14") (pinfunction "RTCM_P$14") (pintype "bidirectional"))
    )
    (net (code "70") (name "unconnected-(U2-P4-Pad4)") (class "Default")
      (node (ref "U2") (pin "4") (pinfunction "P4_4") (pintype "bidirectional"))
    )
    (net (code "71") (name "unconnected-(U4-INT1-Pad6)") (class "Default")
      (node (ref "U4") (pin "6") (pinfunction "INT1_6") (pintype "bidirectional"))
    )
    (net (code "72") (name "unconnected-(U4-INT2-Pad5)") (class "Default")
      (node (ref "U4") (pin "5") (pinfunction "INT2_5") (pintype "bidirectional"))
    )
    (net (code "73") (name "unconnected-(U5-PA13{slash}I13{slash}I2C{slash}SERCOM2+4.1-Pad22)") (class "Default")
      (node (ref "U5") (pin "22") (pinfunction "PA13/I13/I2C/SERCOM2+4.1_22") (pintype "bidirectional"))
    )
    (net (code "74") (name "unconnected-(U5-PA27{slash}I15-Pad39)") (class "Default")
      (node (ref "U5") (pin "39") (pinfunction "PA27/I15_39") (pintype "bidirectional"))
    )
    (net (code "75") (name "unconnected-(U5-PA28{slash}I8-Pad41)") (class "Default")
      (node (ref "U5") (pin "41") (pinfunction "PA28/I8_41") (pintype "bidirectional"))
    )
    (net (code "76") (name "unconnected-(U5-PB03{slash}I3{slash}AIN11{slash}SERCOM5.1-Pad48)") (class "Default")
      (node (ref "U5") (pin "48") (pinfunction "PB03/I3/AIN11/SERCOM5.1_48") (pintype "bidirectional"))
    )
    (net (code "77") (name "unconnected-(U5-PB22{slash}I6{slash}SERCOM5.2-Pad37)") (class "Default")
      (node (ref "U5") (pin "37") (pinfunction "PB22/I6/SERCOM5.2_37") (pintype "bidirectional"))
    )
    (net (code "78") (name "unconnected-(U5-PB23{slash}I7{slash}SERCOM5.3-Pad38)") (class "Default")
      (node (ref "U5") (pin "38") (pinfunction "PB23/I7/SERCOM5.3_38") (pintype "bidirectional"))
    )
    (net (code "79") (name "~{RESET}") (class "Default")
      (node (ref "SW1") (pin "1") (pinfunction "1_1") (pintype "passive"))
      (node (ref "SW1") (pin "2") (pinfunction "2_2") (pintype "passive"))
      (node (ref "U5") (pin "40") (pinfunction "/RESET_40") (pintype "bidirectional"))
    )
  )
)
